# 411_Final_Schematic.net
KiCad netlist of a schematic drawn in EAGLE
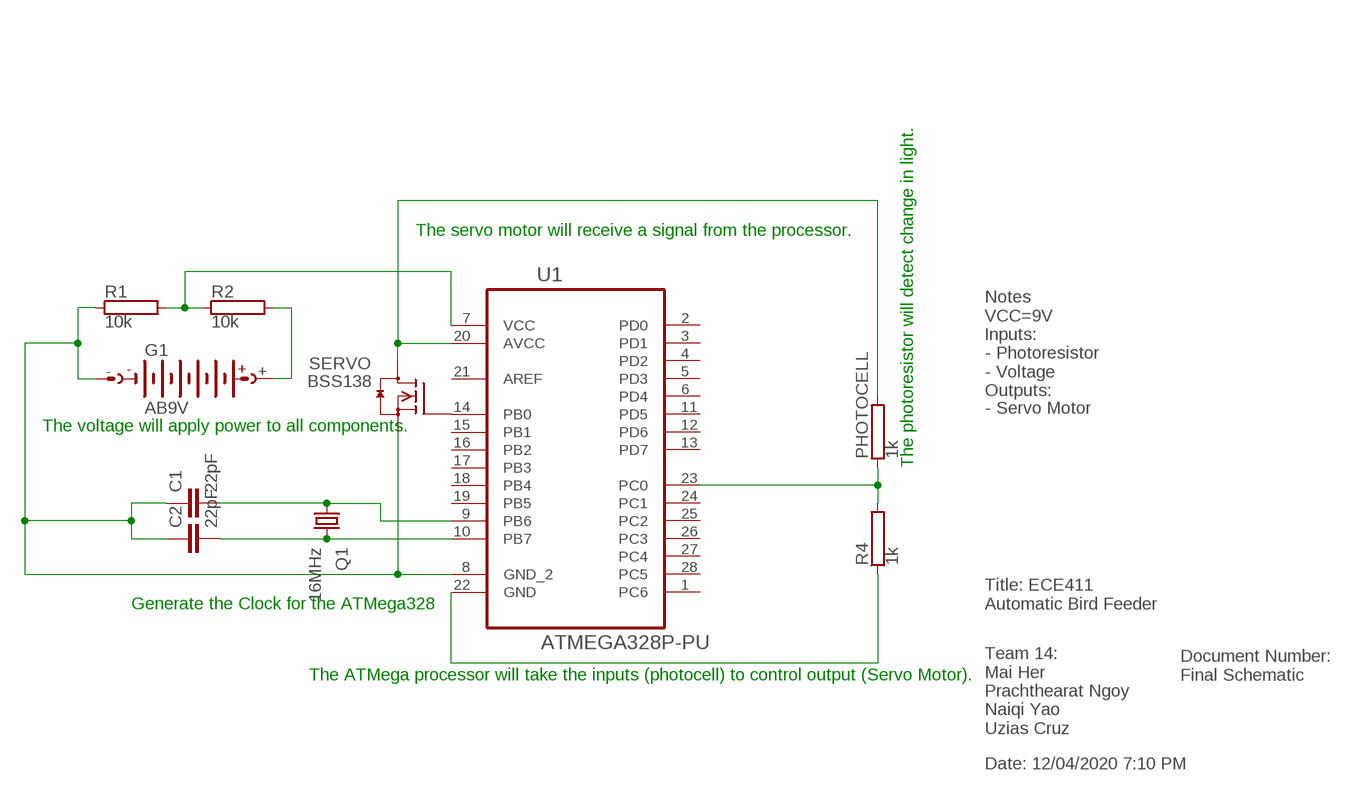
[diagram p0: schematic, sheet 1]

(export (version "E")
  (design (tool "Eeschema 10.0.6"))
  (components
    (comp (ref "C1")
      (value "22pF")
      (footprint "eagle-import:C2.5-3")
      (libsource (lib "eagle-import") (part "C2,5-3"))
    )
    (comp (ref "C2")
      (value "22pF")
      (footprint "eagle-import:C2.5-3")
      (libsource (lib "eagle-import") (part "C2,5-3"))
    )
    (comp (ref "G1")
      (value "AB9V")
      (footprint "eagle-import:AB9V")
      (libsource (lib "eagle-import") (part "AB9V"))
    )
    (comp (ref "PHOTOCELL")
      (value "1k")
      (footprint "eagle-import:AC01")
      (libsource (lib "eagle-import") (part "RAC01"))
    )
    (comp (ref "Q1")
      (value "16MHz")
      (footprint "eagle-import:2.5X2.0_KX-6")
      (libsource (lib "eagle-import") (part "KX-6"))
    )
    (comp (ref "R1")
      (value "10k")
      (footprint "eagle-import:AC01")
      (libsource (lib "eagle-import") (part "RAC01"))
    )
    (comp (ref "R2")
      (value "10k")
      (footprint "eagle-import:AC01")
      (libsource (lib "eagle-import") (part "RAC01"))
    )
    (comp (ref "R4")
      (value "1k")
      (footprint "eagle-import:AC01")
      (libsource (lib "eagle-import") (part "RAC01"))
    )
    (comp (ref "SERVO")
      (value "BSS138")
      (footprint "eagle-import:SOT23")
      (libsource (lib "eagle-import") (part "BSS138"))
    )
    (comp (ref "U1")
      (value "ATMEGA328P-PU")
      (footprint "eagle-import:DIP254P762X457-28")
      (libsource (lib "eagle-import") (part "ATMEGA328P-PU"))
    )
  )
  (nets
    (net (code "1") (name "Net-(G1-Pad+)") (class "Default")
      (node (ref "G1") (pin "+") (pinfunction "+_+") (pintype "passive"))
      (node (ref "R2") (pin "2") (pinfunction "2_2") (pintype "passive"))
    )
    (net (code "2") (name "Net-(Q1-2)") (class "Default")
      (node (ref "C2") (pin "2") (pinfunction "2_2") (pintype "passive"))
      (node (ref "Q1") (pin "3") (pinfunction "2_3") (pintype "passive"))
      (node (ref "U1") (pin "10") (pinfunction "PB7_10") (pintype "bidirectional"))
    )
    (net (code "3") (name "Net-(SERVO-D)") (class "Default")
      (node (ref "PHOTOCELL") (pin "2") (pinfunction "2_2") (pintype "passive"))
      (node (ref "SERVO") (pin "3") (pinfunction "D_3") (pintype "passive"))
      (node (ref "U1") (pin "20") (pinfunction "AVCC_20") (pintype "power_in"))
    )
    (net (code "4") (name "Net-(SERVO-G)") (class "Default")
      (node (ref "SERVO") (pin "1") (pinfunction "G_1") (pintype "passive"))
      (node (ref "U1") (pin "14") (pinfunction "PB0_14") (pintype "bidirectional"))
    )
    (net (code "5") (name "Net-(SERVO-S)") (class "Default")
      (node (ref "C1") (pin "1") (pinfunction "1_1") (pintype "passive"))
      (node (ref "C2") (pin "1") (pinfunction "1_1") (pintype "passive"))
      (node (ref "G1") (pin "-") (pinfunction "-_-") (pintype "passive"))
      (node (ref "R1") (pin "1") (pinfunction "1_1") (pintype "passive"))
      (node (ref "SERVO") (pin "2") (pinfunction "S_2") (pintype "passive"))
      (node (ref "U1") (pin "8") (pinfunction "GND_2_8") (pintype "passive"))
    )
    (net (code "6") (name "Net-(U1-GND)") (class "Default")
      (node (ref "R4") (pin "1") (pinfunction "1_1") (pintype "passive"))
      (node (ref "U1") (pin "22") (pinfunction "GND_22") (pintype "passive"))
    )
    (net (code "7") (name "Net-(U1-PB6)") (class "Default")
      (node (ref "C1") (pin "2") (pinfunction "2_2") (pintype "passive"))
      (node (ref "Q1") (pin "1") (pinfunction "1_1") (pintype "passive"))
      (node (ref "U1") (pin "9") (pinfunction "PB6_9") (pintype "bidirectional"))
    )
    (net (code "8") (name "Net-(U1-PC0)") (class "Default")
      (node (ref "PHOTOCELL") (pin "1") (pinfunction "1_1") (pintype "passive"))
      (node (ref "R4") (pin "2") (pinfunction "2_2") (pintype "passive"))
      (node (ref "U1") (pin "23") (pinfunction "PC0_23") (pintype "bidirectional"))
    )
    (net (code "9") (name "Net-(U1-VCC)") (class "Default")
      (node (ref "R1") (pin "2") (pinfunction "2_2") (pintype "passive"))
      (node (ref "R2") (pin "1") (pinfunction "1_1") (pintype "passive"))
      (node (ref "U1") (pin "7") (pinfunction "VCC_7") (pintype "power_in"))
    )
    (net (code "10") (name "unconnected-(U1-AREF-Pad21)") (class "Default")
      (node (ref "U1") (pin "21") (pinfunction "AREF_21") (pintype "input"))
    )
    (net (code "11") (name "unconnected-(U1-PB1-Pad15)") (class "Default")
      (node (ref "U1") (pin "15") (pinfunction "PB1_15") (pintype "bidirectional"))
    )
    (net (code "12") (name "unconnected-(U1-PB2-Pad16)") (class "Default")
      (node (ref "U1") (pin "16") (pinfunction "PB2_16") (pintype "bidirectional"))
    )
    (net (code "13") (name "unconnected-(U1-PB3-Pad17)") (class "Default")
      (node (ref "U1") (pin "17") (pinfunction "PB3_17") (pintype "bidirectional"))
    )
    (net (code "14") (name "unconnected-(U1-PB4-Pad18)") (class "Default")
      (node (ref "U1") (pin "18") (pinfunction "PB4_18") (pintype "bidirectional"))
    )
    (net (code "15") (name "unconnected-(U1-PB5-Pad19)") (class "Default")
      (node (ref "U1") (pin "19") (pinfunction "PB5_19") (pintype "bidirectional"))
    )
    (net (code "16") (name "unconnected-(U1-PC1-Pad24)") (class "Default")
      (node (ref "U1") (pin "24") (pinfunction "PC1_24") (pintype "bidirectional"))
    )
    (net (code "17") (name "unconnected-(U1-PC2-Pad25)") (class "Default")
      (node (ref "U1") (pin "25") (pinfunction "PC2_25") (pintype "bidirectional"))
    )
    (net (code "18") (name "unconnected-(U1-PC3-Pad26)") (class "Default")
      (node (ref "U1") (pin "26") (pinfunction "PC3_26") (pintype "bidirectional"))
    )
    (net (code "19") (name "unconnected-(U1-PC4-Pad27)") (class "Default")
      (node (ref "U1") (pin "27") (pinfunction "PC4_27") (pintype "bidirectional"))
    )
    (net (code "20") (name "unconnected-(U1-PC5-Pad28)") (class "Default")
      (node (ref "U1") (pin "28") (pinfunction "PC5_28") (pintype "bidirectional"))
    )
    (net (code "21") (name "unconnected-(U1-PC6-Pad1)") (class "Default")
      (node (ref "U1") (pin "1") (pinfunction "PC6_1") (pintype "bidirectional"))
    )
    (net (code "22") (name "unconnected-(U1-PD0-Pad2)") (class "Default")
      (node (ref "U1") (pin "2") (pinfunction "PD0_2") (pintype "bidirectional"))
    )
    (net (code "23") (name "unconnected-(U1-PD1-Pad3)") (class "Default")
      (node (ref "U1") (pin "3") (pinfunction "PD1_3") (pintype "bidirectional"))
    )
    (net (code "24") (name "unconnected-(U1-PD2-Pad4)") (class "Default")
      (node (ref "U1") (pin "4") (pinfunction "PD2_4") (pintype "bidirectional"))
    )
    (net (code "25") (name "unconnected-(U1-PD3-Pad5)") (class "Default")
      (node (ref "U1") (pin "5") (pinfunction "PD3_5") (pintype "bidirectional"))
    )
    (net (code "26") (name "unconnected-(U1-PD4-Pad6)") (class "Default")
      (node (ref "U1") (pin "6") (pinfunction "PD4_6") (pintype "bidirectional"))
    )
    (net (code "27") (name "unconnected-(U1-PD5-Pad11)") (class "Default")
      (node (ref "U1") (pin "11") (pinfunction "PD5_11") (pintype "bidirectional"))
    )
    (net (code "28") (name "unconnected-(U1-PD6-Pad12)") (class "Default")
      (node (ref "U1") (pin "12") (pinfunction "PD6_12") (pintype "bidirectional"))
    )
    (net (code "29") (name "unconnected-(U1-PD7-Pad13)") (class "Default")
      (node (ref "U1") (pin "13") (pinfunction "PD7_13") (pintype "bidirectional"))
    )
  )
)
